# CAN_Bus_Controller_with_LED_Lamp_Drivers.net
KiCad netlist of a schematic drawn in EAGLE
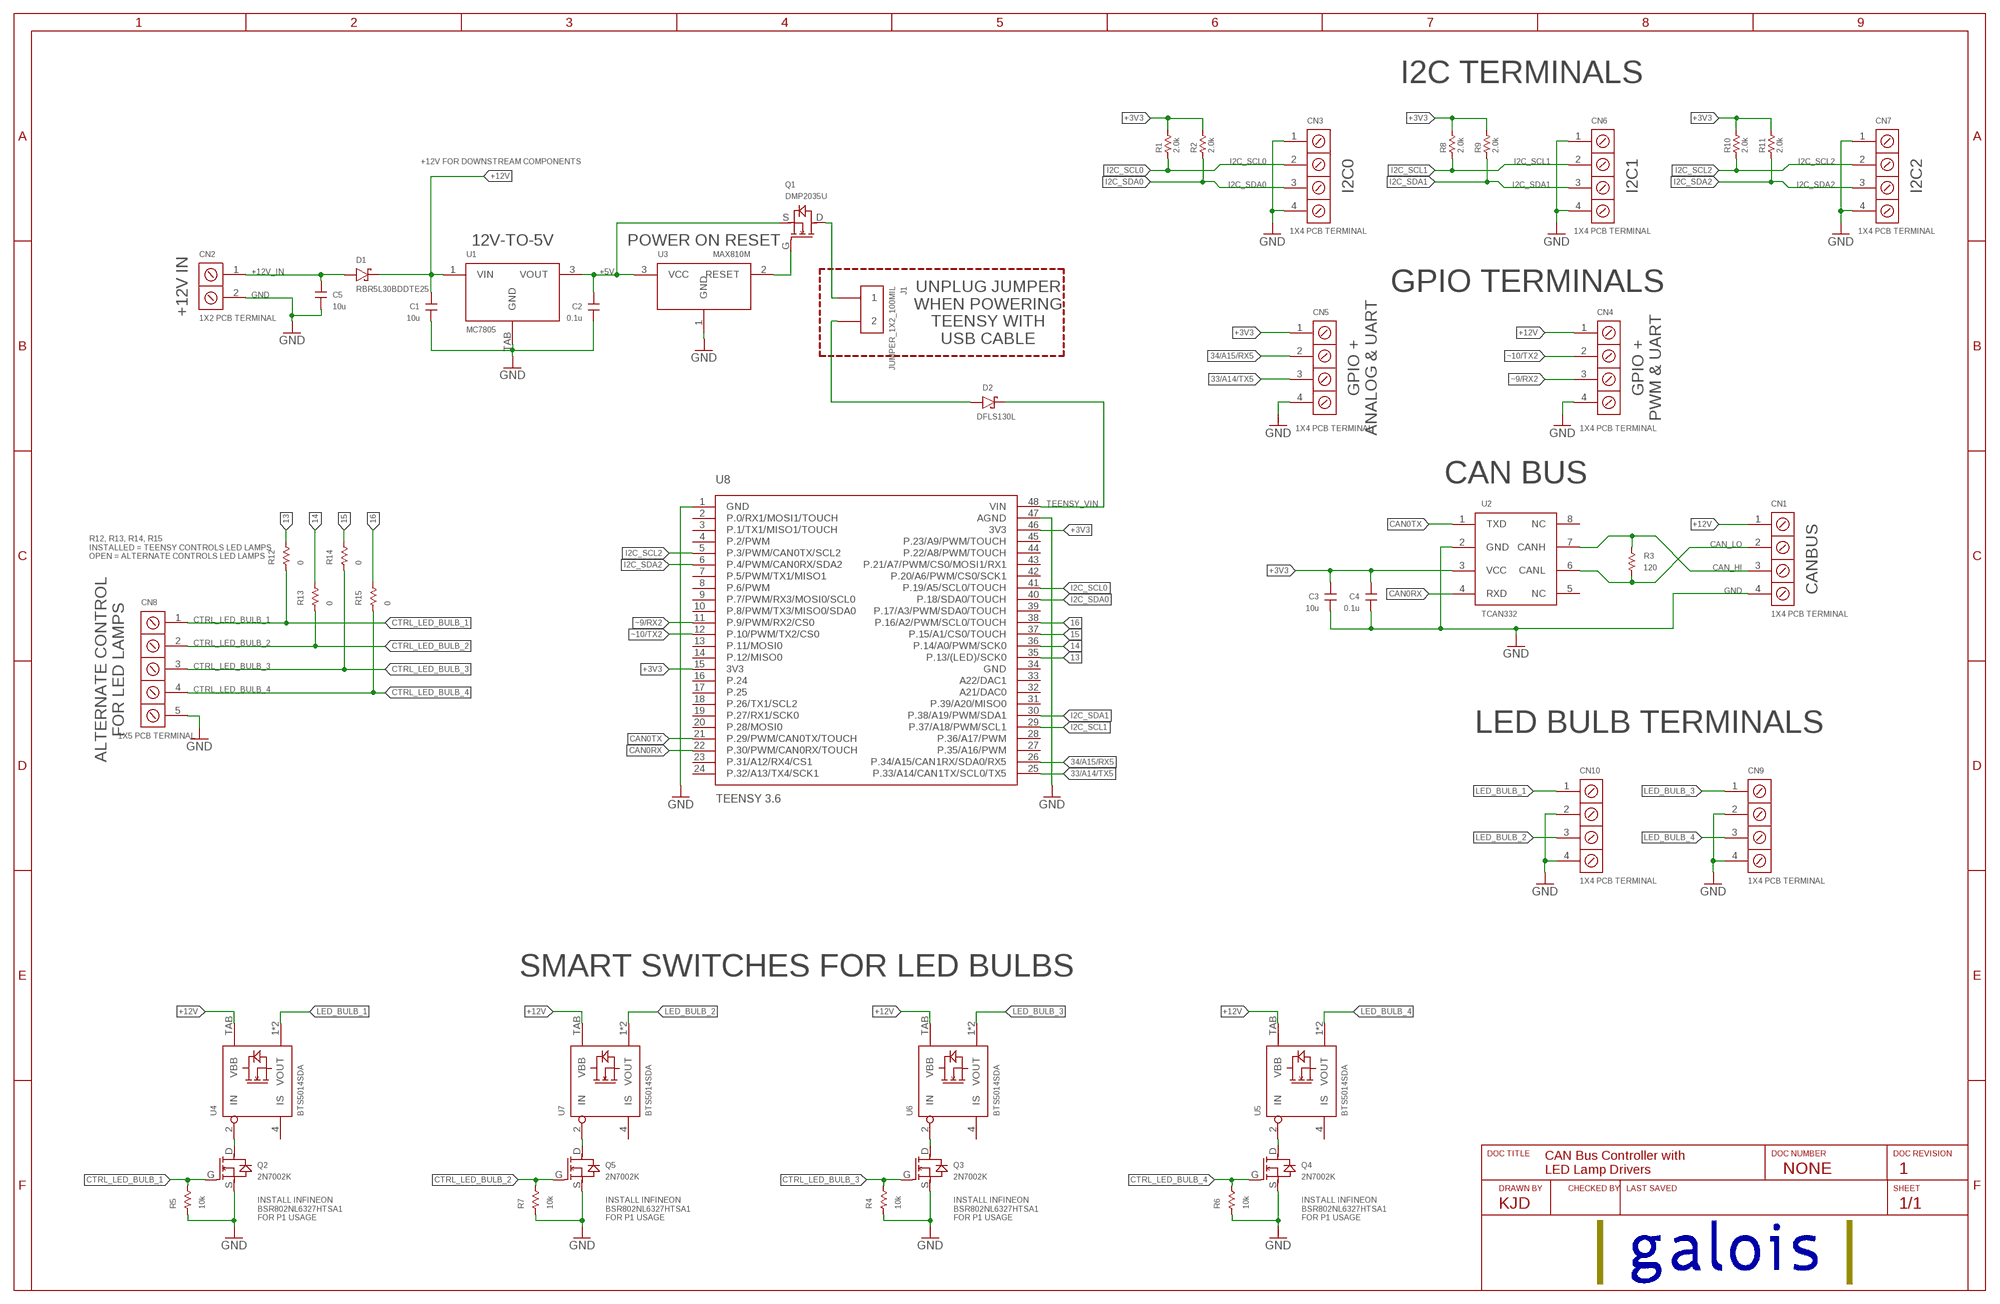
[diagram p0: schematic, sheet 1]

(export (version "E")
  (design (tool "Eeschema 10.0.6"))
  (components
    (comp (ref "C1")
      (value "10u")
      (footprint "eagle-import:EIA1206")
      (fields (field (name "MPN") "CL31A106KBHNNNE"))
      (libsource (lib "eagle-import") (part "C_SMDC1206"))
    )
    (comp (ref "C2")
      (value "0.1u")
      (footprint "eagle-import:EIA0603")
      (fields (field (name "MPN") "CL10B104KA8NNNC"))
      (libsource (lib "eagle-import") (part "C_SMDC0603"))
    )
    (comp (ref "C3")
      (value "10u")
      (footprint "eagle-import:EIA1206")
      (fields (field (name "MPN") "CL31A106KBHNNNE"))
      (libsource (lib "eagle-import") (part "C_SMDC1206"))
    )
    (comp (ref "C4")
      (value "0.1u")
      (footprint "eagle-import:EIA0603")
      (fields (field (name "MPN") "CL10B104KA8NNNC"))
      (libsource (lib "eagle-import") (part "C_SMDC0603"))
    )
    (comp (ref "C5")
      (value "10u")
      (footprint "eagle-import:EIA1206")
      (fields (field (name "MPN") "CL31A106KBHNNNE"))
      (libsource (lib "eagle-import") (part "C_SMDC1206"))
    )
    (comp (ref "CN1")
      (value "1X4 PCB TERMINAL")
      (footprint "eagle-import:PCB_TERM_3.5MM_PITCH_1X4")
      (fields (field (name "MPN") "1984633"))
      (libsource (lib "eagle-import") (part "1984633"))
    )
    (comp (ref "CN2")
      (value "1X2 PCB TERMINAL")
      (footprint "eagle-import:PCB_TERM_3.5MM_PITCH_1X2")
      (fields (field (name "MPN") "1984617"))
      (libsource (lib "eagle-import") (part "1984617"))
    )
    (comp (ref "CN3")
      (value "1X4 PCB TERMINAL")
      (footprint "eagle-import:PCB_TERM_3.5MM_PITCH_1X4")
      (fields (field (name "MPN") "1984633"))
      (libsource (lib "eagle-import") (part "1984633"))
    )
    (comp (ref "CN4")
      (value "1X4 PCB TERMINAL")
      (footprint "eagle-import:PCB_TERM_3.5MM_PITCH_1X4")
      (fields (field (name "MPN") "1984633"))
      (libsource (lib "eagle-import") (part "1984633"))
    )
    (comp (ref "CN5")
      (value "1X4 PCB TERMINAL")
      (footprint "eagle-import:PCB_TERM_3.5MM_PITCH_1X4")
      (fields (field (name "MPN") "1984633"))
      (libsource (lib "eagle-import") (part "1984633"))
    )
    (comp (ref "CN6")
      (value "1X4 PCB TERMINAL")
      (footprint "eagle-import:PCB_TERM_3.5MM_PITCH_1X4")
      (fields (field (name "MPN") "1984633"))
      (libsource (lib "eagle-import") (part "1984633"))
    )
    (comp (ref "CN7")
      (value "1X4 PCB TERMINAL")
      (footprint "eagle-import:PCB_TERM_3.5MM_PITCH_1X4")
      (fields (field (name "MPN") "1984633"))
      (libsource (lib "eagle-import") (part "1984633"))
    )
    (comp (ref "CN8")
      (value "1X5 PCB TERMINAL")
      (footprint "eagle-import:PCB_TERM_3.5MM_PITCH_1X5")
      (fields (field (name "MPN") "1984646"))
      (libsource (lib "eagle-import") (part "1984646"))
    )
    (comp (ref "CN9")
      (value "1X4 PCB TERMINAL")
      (footprint "eagle-import:PCB_TERM_3.5MM_PITCH_1X4")
      (fields (field (name "MPN") "1984633"))
      (libsource (lib "eagle-import") (part "1984633"))
    )
    (comp (ref "CN10")
      (value "1X4 PCB TERMINAL")
      (footprint "eagle-import:PCB_TERM_3.5MM_PITCH_1X4")
      (fields (field (name "MPN") "1984633"))
      (libsource (lib "eagle-import") (part "1984633"))
    )
    (comp (ref "D1")
      (value "RBR5L30BDDTE25")
      (footprint "eagle-import:SMA")
      (fields (field (name "MPN") "RBR5L30BDDTE25"))
      (libsource (lib "eagle-import") (part "SCHOTTKYSMA"))
    )
    (comp (ref "D2")
      (value "DFLS130L")
      (footprint "eagle-import:POWERDI_123")
      (fields (field (name "MPN") "DFLS130L-7"))
      (libsource (lib "eagle-import") (part "SCHOTTKYPOWERDI_123"))
    )
    (comp (ref "J1")
      (value "JUMPER_1X2_100MIL")
      (footprint "eagle-import:1X2_100MIL_THRU")
      (fields (field (name "MPN") "QPC02SXGN-RC"))
      (libsource (lib "eagle-import") (part "1X2"))
    )
    (comp (ref "Q1")
      (value "DMP2035U")
      (footprint "eagle-import:SOT-23-3")
      (fields (field (name "MPN") "DMP2035U-7"))
      (libsource (lib "eagle-import") (part "DMP2035U"))
    )
    (comp (ref "Q2")
      (value "2N7002K")
      (footprint "eagle-import:SOT-23-3")
      (fields (field (name "MPN") "2N7002K-7"))
      (libsource (lib "eagle-import") (part "2N7002K"))
    )
    (comp (ref "Q3")
      (value "2N7002K")
      (footprint "eagle-import:SOT-23-3")
      (fields (field (name "MPN") "2N7002K-7"))
      (libsource (lib "eagle-import") (part "2N7002K"))
    )
    (comp (ref "Q4")
      (value "2N7002K")
      (footprint "eagle-import:SOT-23-3")
      (fields (field (name "MPN") "2N7002K-7"))
      (libsource (lib "eagle-import") (part "2N7002K"))
    )
    (comp (ref "Q5")
      (value "2N7002K")
      (footprint "eagle-import:SOT-23-3")
      (fields (field (name "MPN") "2N7002K-7"))
      (libsource (lib "eagle-import") (part "2N7002K"))
    )
    (comp (ref "R1")
      (value "2.0k")
      (footprint "eagle-import:EIA0603")
      (fields (field (name "MPN") "ERJ-3EKF2001V"))
      (libsource (lib "eagle-import") (part "R_SMDR0603"))
    )
    (comp (ref "R2")
      (value "2.0k")
      (footprint "eagle-import:EIA0603")
      (fields (field (name "MPN") "ERJ-3EKF2001V"))
      (libsource (lib "eagle-import") (part "R_SMDR0603"))
    )
    (comp (ref "R3")
      (value "120")
      (footprint "eagle-import:EIA1210")
      (fields (field (name "MPN") "AC1210FR-07120RL"))
      (libsource (lib "eagle-import") (part "R_SMDR1210"))
    )
    (comp (ref "R4")
      (value "10k")
      (footprint "eagle-import:EIA0603")
      (fields (field (name "MPN") "ERJ-3EKF1002V"))
      (libsource (lib "eagle-import") (part "R_SMDR0603"))
    )
    (comp (ref "R5")
      (value "10k")
      (footprint "eagle-import:EIA0603")
      (fields (field (name "MPN") "ERJ-3EKF1002V"))
      (libsource (lib "eagle-import") (part "R_SMDR0603"))
    )
    (comp (ref "R6")
      (value "10k")
      (footprint "eagle-import:EIA0603")
      (fields (field (name "MPN") "ERJ-3EKF1002V"))
      (libsource (lib "eagle-import") (part "R_SMDR0603"))
    )
    (comp (ref "R7")
      (value "10k")
      (footprint "eagle-import:EIA0603")
      (fields (field (name "MPN") "ERJ-3EKF1002V"))
      (libsource (lib "eagle-import") (part "R_SMDR0603"))
    )
    (comp (ref "R8")
      (value "2.0k")
      (footprint "eagle-import:EIA0603")
      (fields (field (name "MPN") "ERJ-3EKF2001V"))
      (libsource (lib "eagle-import") (part "R_SMDR0603"))
    )
    (comp (ref "R9")
      (value "2.0k")
      (footprint "eagle-import:EIA0603")
      (fields (field (name "MPN") "ERJ-3EKF2001V"))
      (libsource (lib "eagle-import") (part "R_SMDR0603"))
    )
    (comp (ref "R10")
      (value "2.0k")
      (footprint "eagle-import:EIA0603")
      (fields (field (name "MPN") "ERJ-3EKF2001V"))
      (libsource (lib "eagle-import") (part "R_SMDR0603"))
    )
    (comp (ref "R11")
      (value "2.0k")
      (footprint "eagle-import:EIA0603")
      (fields (field (name "MPN") "ERJ-3EKF2001V"))
      (libsource (lib "eagle-import") (part "R_SMDR0603"))
    )
    (comp (ref "R12")
      (value "0")
      (footprint "eagle-import:EIA0603")
      (fields (field (name "MPN") "ERJ-3GEY0R00V"))
      (libsource (lib "eagle-import") (part "R_SMDR0603"))
    )
    (comp (ref "R13")
      (value "0")
      (footprint "eagle-import:EIA0603")
      (fields (field (name "MPN") "ERJ-3GEY0R00V"))
      (libsource (lib "eagle-import") (part "R_SMDR0603"))
    )
    (comp (ref "R14")
      (value "0")
      (footprint "eagle-import:EIA0603")
      (fields (field (name "MPN") "ERJ-3GEY0R00V"))
      (libsource (lib "eagle-import") (part "R_SMDR0603"))
    )
    (comp (ref "R15")
      (value "0")
      (footprint "eagle-import:EIA0603")
      (fields (field (name "MPN") "ERJ-3GEY0R00V"))
      (libsource (lib "eagle-import") (part "R_SMDR0603"))
    )
    (comp (ref "U1")
      (value "MC7805")
      (footprint "eagle-import:DPAK-3")
      (fields (field (name "MPN") "MC7805CDTRKG"))
      (libsource (lib "eagle-import") (part "MC78XX"))
    )
    (comp (ref "U2")
      (value "TCAN332")
      (footprint "eagle-import:SOIC-8")
      (fields (field (name "MPN") "TCAN332DR"))
      (libsource (lib "eagle-import") (part "TCAN332_CANBUS_RXTX"))
    )
    (comp (ref "U3")
      (value "MAX810M")
      (footprint "eagle-import:SOT23-3")
      (fields (field (name "MPN") "MAX810MTRG"))
      (libsource (lib "eagle-import") (part "MAX809/810"))
    )
    (comp (ref "U4")
      (value "BTS5014SDA")
      (footprint "eagle-import:PG-TO252-5-11")
      (fields (field (name "MPN") "BTS5014SDAAUMA1"))
      (libsource (lib "eagle-import") (part "BTS5014SDA"))
    )
    (comp (ref "U5")
      (value "BTS5014SDA")
      (footprint "eagle-import:PG-TO252-5-11")
      (fields (field (name "MPN") "BTS5014SDAAUMA1"))
      (libsource (lib "eagle-import") (part "BTS5014SDA"))
    )
    (comp (ref "U6")
      (value "BTS5014SDA")
      (footprint "eagle-import:PG-TO252-5-11")
      (fields (field (name "MPN") "BTS5014SDAAUMA1"))
      (libsource (lib "eagle-import") (part "BTS5014SDA"))
    )
    (comp (ref "U7")
      (value "BTS5014SDA")
      (footprint "eagle-import:PG-TO252-5-11")
      (fields (field (name "MPN") "BTS5014SDAAUMA1"))
      (libsource (lib "eagle-import") (part "BTS5014SDA"))
    )
    (comp (ref "U8")
      (value "TEENSY 3.6")
      (footprint "eagle-import:TEENSY3.6")
      (libsource (lib "eagle-import") (part "TEENSY3.6NO_UNDER_PINS"))
    )
  )
  (nets
    (net (code "1") (name "+3V3") (class "Default")
      (node (ref "C3") (pin "P$2") (pinfunction "P$2_P$2") (pintype "passive"))
      (node (ref "C4") (pin "P$2") (pinfunction "P$2_P$2") (pintype "passive"))
      (node (ref "CN5") (pin "1") (pinfunction "1_1") (pintype "bidirectional"))
      (node (ref "R1") (pin "P$2") (pinfunction "P$2_P$2") (pintype "passive"))
      (node (ref "R10") (pin "P$2") (pinfunction "P$2_P$2") (pintype "passive"))
      (node (ref "R11") (pin "P$2") (pinfunction "P$2_P$2") (pintype "passive"))
      (node (ref "R2") (pin "P$2") (pinfunction "P$2_P$2") (pintype "passive"))
      (node (ref "R8") (pin "P$2") (pinfunction "P$2_P$2") (pintype "passive"))
      (node (ref "R9") (pin "P$2") (pinfunction "P$2_P$2") (pintype "passive"))
      (node (ref "U2") (pin "3") (pinfunction "VCC_3") (pintype "bidirectional"))
      (node (ref "U8") (pin "15") (pinfunction "3V3_15") (pintype "bidirectional"))
      (node (ref "U8") (pin "46") (pinfunction "3V3_46") (pintype "bidirectional"))
    )
    (net (code "2") (name "+12V") (class "Default")
      (node (ref "C1") (pin "P$2") (pinfunction "P$2_P$2") (pintype "passive"))
      (node (ref "CN1") (pin "1") (pinfunction "1_1") (pintype "bidirectional"))
      (node (ref "CN4") (pin "1") (pinfunction "1_1") (pintype "bidirectional"))
      (node (ref "D1") (pin "C") (pinfunction "C_C") (pintype "bidirectional"))
      (node (ref "U1") (pin "1") (pinfunction "VIN_1") (pintype "bidirectional"))
      (node (ref "U4") (pin "TAB") (pinfunction "VBB_TAB") (pintype "bidirectional"))
      (node (ref "U5") (pin "TAB") (pinfunction "VBB_TAB") (pintype "bidirectional"))
      (node (ref "U6") (pin "TAB") (pinfunction "VBB_TAB") (pintype "bidirectional"))
      (node (ref "U7") (pin "TAB") (pinfunction "VBB_TAB") (pintype "bidirectional"))
    )
    (net (code "3") (name "/+5V") (class "Default")
      (node (ref "C2") (pin "P$2") (pinfunction "P$2_P$2") (pintype "passive"))
      (node (ref "Q1") (pin "S") (pinfunction "S_S") (pintype "bidirectional"))
      (node (ref "U1") (pin "3") (pinfunction "VOUT_3") (pintype "bidirectional"))
      (node (ref "U3") (pin "3") (pinfunction "VCC_3") (pintype "bidirectional"))
    )
    (net (code "4") (name "/+12V_IN") (class "Default")
      (node (ref "C5") (pin "P$2") (pinfunction "P$2_P$2") (pintype "passive"))
      (node (ref "CN2") (pin "1") (pinfunction "1_1") (pintype "bidirectional"))
      (node (ref "D1") (pin "A") (pinfunction "A_A") (pintype "bidirectional"))
    )
    (net (code "5") (name "/CAN_HI") (class "Default")
      (node (ref "CN1") (pin "3") (pinfunction "3_3") (pintype "bidirectional"))
      (node (ref "R3") (pin "P$2") (pinfunction "P$2_P$2") (pintype "passive"))
      (node (ref "U2") (pin "7") (pinfunction "CANH_7") (pintype "bidirectional"))
    )
    (net (code "6") (name "/CAN_LO") (class "Default")
      (node (ref "CN1") (pin "2") (pinfunction "2_2") (pintype "bidirectional"))
      (node (ref "R3") (pin "P$1") (pinfunction "P$1_P$1") (pintype "passive"))
      (node (ref "U2") (pin "6") (pinfunction "CANL_6") (pintype "bidirectional"))
    )
    (net (code "7") (name "/TEENSY_VIN") (class "Default")
      (node (ref "D2") (pin "C") (pinfunction "C_C") (pintype "bidirectional"))
      (node (ref "U8") (pin "48") (pinfunction "VIN_48") (pintype "bidirectional"))
    )
    (net (code "8") (name "/~{9{slash}RX2}") (class "Default")
      (node (ref "CN4") (pin "3") (pinfunction "3_3") (pintype "bidirectional"))
      (node (ref "U8") (pin "11") (pinfunction "P.9/PWM/RX2/CS0_11") (pintype "bidirectional"))
    )
    (net (code "9") (name "/~{10{slash}TX2}") (class "Default")
      (node (ref "CN4") (pin "2") (pinfunction "2_2") (pintype "bidirectional"))
      (node (ref "U8") (pin "12") (pinfunction "P.10/PWM/TX2/CS0_12") (pintype "bidirectional"))
    )
    (net (code "10") (name "13") (class "Default")
      (node (ref "R12") (pin "P$2") (pinfunction "P$2_P$2") (pintype "passive"))
      (node (ref "U8") (pin "35") (pinfunction "P.13/(LED)/SCK0_35") (pintype "bidirectional"))
    )
    (net (code "11") (name "14") (class "Default")
      (node (ref "R13") (pin "P$2") (pinfunction "P$2_P$2") (pintype "passive"))
      (node (ref "U8") (pin "36") (pinfunction "P.14/A0/PWM/SCK0_36") (pintype "bidirectional"))
    )
    (net (code "12") (name "15") (class "Default")
      (node (ref "R14") (pin "P$2") (pinfunction "P$2_P$2") (pintype "passive"))
      (node (ref "U8") (pin "37") (pinfunction "P.15/A1/CS0/TOUCH_37") (pintype "bidirectional"))
    )
    (net (code "13") (name "16") (class "Default")
      (node (ref "R15") (pin "P$2") (pinfunction "P$2_P$2") (pintype "passive"))
      (node (ref "U8") (pin "38") (pinfunction "P.16/A2/PWM/SCL0/TOUCH_38") (pintype "bidirectional"))
    )
    (net (code "14") (name "33{slash}A14{slash}TX5") (class "Default")
      (node (ref "CN5") (pin "3") (pinfunction "3_3") (pintype "bidirectional"))
      (node (ref "U8") (pin "25") (pinfunction "P.33/A14/CAN1TX/SCL0/TX5_25") (pintype "bidirectional"))
    )
    (net (code "15") (name "34{slash}A15{slash}RX5") (class "Default")
      (node (ref "CN5") (pin "2") (pinfunction "2_2") (pintype "bidirectional"))
      (node (ref "U8") (pin "26") (pinfunction "P.34/A15/CAN1RX/SDA0/RX5_26") (pintype "bidirectional"))
    )
    (net (code "16") (name "CAN0RX") (class "Default")
      (node (ref "U2") (pin "4") (pinfunction "RXD_4") (pintype "bidirectional"))
      (node (ref "U8") (pin "22") (pinfunction "P.30/PWM/CAN0RX/TOUCH_22") (pintype "bidirectional"))
    )
    (net (code "17") (name "CAN0TX") (class "Default")
      (node (ref "U2") (pin "1") (pinfunction "TXD_1") (pintype "bidirectional"))
      (node (ref "U8") (pin "21") (pinfunction "P.29/PWM/CAN0TX/TOUCH_21") (pintype "bidirectional"))
    )
    (net (code "18") (name "CTRL_LED_BULB_1") (class "Default")
      (node (ref "CN8") (pin "1") (pinfunction "1_1") (pintype "bidirectional"))
      (node (ref "Q2") (pin "G") (pinfunction "G_G") (pintype "bidirectional"))
      (node (ref "R12") (pin "P$1") (pinfunction "P$1_P$1") (pintype "passive"))
      (node (ref "R5") (pin "P$2") (pinfunction "P$2_P$2") (pintype "passive"))
    )
    (net (code "19") (name "CTRL_LED_BULB_2") (class "Default")
      (node (ref "CN8") (pin "2") (pinfunction "2_2") (pintype "bidirectional"))
      (node (ref "Q5") (pin "G") (pinfunction "G_G") (pintype "bidirectional"))
      (node (ref "R13") (pin "P$1") (pinfunction "P$1_P$1") (pintype "passive"))
      (node (ref "R7") (pin "P$2") (pinfunction "P$2_P$2") (pintype "passive"))
    )
    (net (code "20") (name "CTRL_LED_BULB_3") (class "Default")
      (node (ref "CN8") (pin "3") (pinfunction "3_3") (pintype "bidirectional"))
      (node (ref "Q3") (pin "G") (pinfunction "G_G") (pintype "bidirectional"))
      (node (ref "R14") (pin "P$1") (pinfunction "P$1_P$1") (pintype "passive"))
      (node (ref "R4") (pin "P$2") (pinfunction "P$2_P$2") (pintype "passive"))
    )
    (net (code "21") (name "CTRL_LED_BULB_4") (class "Default")
      (node (ref "CN8") (pin "4") (pinfunction "4_4") (pintype "bidirectional"))
      (node (ref "Q4") (pin "G") (pinfunction "G_G") (pintype "bidirectional"))
      (node (ref "R15") (pin "P$1") (pinfunction "P$1_P$1") (pintype "passive"))
      (node (ref "R6") (pin "P$2") (pinfunction "P$2_P$2") (pintype "passive"))
    )
    (net (code "22") (name "GND") (class "Default")
      (node (ref "C1") (pin "P$1") (pinfunction "P$1_P$1") (pintype "passive"))
      (node (ref "C2") (pin "P$1") (pinfunction "P$1_P$1") (pintype "passive"))
      (node (ref "C3") (pin "P$1") (pinfunction "P$1_P$1") (pintype "passive"))
      (node (ref "C4") (pin "P$1") (pinfunction "P$1_P$1") (pintype "passive"))
      (node (ref "C5") (pin "P$1") (pinfunction "P$1_P$1") (pintype "passive"))
      (node (ref "CN1") (pin "4") (pinfunction "4_4") (pintype "bidirectional"))
      (node (ref "CN10") (pin "2") (pinfunction "2_2") (pintype "bidirectional"))
      (node (ref "CN10") (pin "4") (pinfunction "4_4") (pintype "bidirectional"))
      (node (ref "CN2") (pin "2") (pinfunction "2_2") (pintype "bidirectional"))
      (node (ref "CN3") (pin "1") (pinfunction "1_1") (pintype "bidirectional"))
      (node (ref "CN3") (pin "4") (pinfunction "4_4") (pintype "bidirectional"))
      (node (ref "CN4") (pin "4") (pinfunction "4_4") (pintype "bidirectional"))
      (node (ref "CN5") (pin "4") (pinfunction "4_4") (pintype "bidirectional"))
      (node (ref "CN6") (pin "1") (pinfunction "1_1") (pintype "bidirectional"))
      (node (ref "CN6") (pin "4") (pinfunction "4_4") (pintype "bidirectional"))
      (node (ref "CN7") (pin "1") (pinfunction "1_1") (pintype "bidirectional"))
      (node (ref "CN7") (pin "4") (pinfunction "4_4") (pintype "bidirectional"))
      (node (ref "CN8") (pin "5") (pinfunction "5_5") (pintype "bidirectional"))
      (node (ref "CN9") (pin "2") (pinfunction "2_2") (pintype "bidirectional"))
      (node (ref "CN9") (pin "4") (pinfunction "4_4") (pintype "bidirectional"))
      (node (ref "Q2") (pin "S") (pinfunction "S_S") (pintype "bidirectional"))
      (node (ref "Q3") (pin "S") (pinfunction "S_S") (pintype "bidirectional"))
      (node (ref "Q4") (pin "S") (pinfunction "S_S") (pintype "bidirectional"))
      (node (ref "Q5") (pin "S") (pinfunction "S_S") (pintype "bidirectional"))
      (node (ref "R4") (pin "P$1") (pinfunction "P$1_P$1") (pintype "passive"))
      (node (ref "R5") (pin "P$1") (pinfunction "P$1_P$1") (pintype "passive"))
      (node (ref "R6") (pin "P$1") (pinfunction "P$1_P$1") (pintype "passive"))
      (node (ref "R7") (pin "P$1") (pinfunction "P$1_P$1") (pintype "passive"))
      (node (ref "U1") (pin "TAB") (pinfunction "GND_TAB") (pintype "bidirectional"))
      (node (ref "U2") (pin "2") (pinfunction "GND_2") (pintype "bidirectional"))
      (node (ref "U3") (pin "1") (pinfunction "GND_1") (pintype "bidirectional"))
      (node (ref "U8") (pin "1") (pinfunction "GND_1") (pintype "bidirectional"))
      (node (ref "U8") (pin "47") (pinfunction "AGND_47") (pintype "bidirectional"))
    )
    (net (code "23") (name "I2C_SCL0") (class "Default")
      (node (ref "CN3") (pin "2") (pinfunction "2_2") (pintype "bidirectional"))
      (node (ref "R1") (pin "P$1") (pinfunction "P$1_P$1") (pintype "passive"))
      (node (ref "U8") (pin "41") (pinfunction "P.19/A5/SCL0/TOUCH_41") (pintype "bidirectional"))
    )
    (net (code "24") (name "I2C_SCL1") (class "Default")
      (node (ref "CN6") (pin "2") (pinfunction "2_2") (pintype "bidirectional"))
      (node (ref "R8") (pin "P$1") (pinfunction "P$1_P$1") (pintype "passive"))
      (node (ref "U8") (pin "29") (pinfunction "P.37/A18/PWM/SCL1_29") (pintype "bidirectional"))
    )
    (net (code "25") (name "I2C_SCL2") (class "Default")
      (node (ref "CN7") (pin "2") (pinfunction "2_2") (pintype "bidirectional"))
      (node (ref "R10") (pin "P$1") (pinfunction "P$1_P$1") (pintype "passive"))
      (node (ref "U8") (pin "5") (pinfunction "P.3/PWM/CAN0TX/SCL2_5") (pintype "bidirectional"))
    )
    (net (code "26") (name "I2C_SDA0") (class "Default")
      (node (ref "CN3") (pin "3") (pinfunction "3_3") (pintype "bidirectional"))
      (node (ref "R2") (pin "P$1") (pinfunction "P$1_P$1") (pintype "passive"))
      (node (ref "U8") (pin "40") (pinfunction "P.18/SDA0/TOUCH_40") (pintype "bidirectional"))
    )
    (net (code "27") (name "I2C_SDA1") (class "Default")
      (node (ref "CN6") (pin "3") (pinfunction "3_3") (pintype "bidirectional"))
      (node (ref "R9") (pin "P$1") (pinfunction "P$1_P$1") (pintype "passive"))
      (node (ref "U8") (pin "30") (pinfunction "P.38/A19/PWM/SDA1_30") (pintype "bidirectional"))
    )
    (net (code "28") (name "I2C_SDA2") (class "Default")
      (node (ref "CN7") (pin "3") (pinfunction "3_3") (pintype "bidirectional"))
      (node (ref "R11") (pin "P$1") (pinfunction "P$1_P$1") (pintype "passive"))
      (node (ref "U8") (pin "6") (pinfunction "P.4/PWM/CAN0RX/SDA2_6") (pintype "bidirectional"))
    )
    (net (code "29") (name "LED_BULB_1") (class "Default")
      (node (ref "CN10") (pin "1") (pinfunction "1_1") (pintype "bidirectional"))
      (node (ref "U4") (pin "1") (pinfunction "VOUT_1") (pintype "bidirectional"))
      (node (ref "U4") (pin "5") (pinfunction "VOUT_5") (pintype "bidirectional"))
    )
    (net (code "30") (name "LED_BULB_2") (class "Default")
      (node (ref "CN10") (pin "3") (pinfunction "3_3") (pintype "bidirectional"))
      (node (ref "U7") (pin "1") (pinfunction "VOUT_1") (pintype "bidirectional"))
      (node (ref "U7") (pin "5") (pinfunction "VOUT_5") (pintype "bidirectional"))
    )
    (net (code "31") (name "LED_BULB_3") (class "Default")
      (node (ref "CN9") (pin "1") (pinfunction "1_1") (pintype "bidirectional"))
      (node (ref "U6") (pin "1") (pinfunction "VOUT_1") (pintype "bidirectional"))
      (node (ref "U6") (pin "5") (pinfunction "VOUT_5") (pintype "bidirectional"))
    )
    (net (code "32") (name "LED_BULB_4") (class "Default")
      (node (ref "CN9") (pin "3") (pinfunction "3_3") (pintype "bidirectional"))
      (node (ref "U5") (pin "1") (pinfunction "VOUT_1") (pintype "bidirectional"))
      (node (ref "U5") (pin "5") (pinfunction "VOUT_5") (pintype "bidirectional"))
    )
    (net (code "33") (name "Net-(D2-PadA)") (class "Default")
      (node (ref "D2") (pin "A") (pinfunction "A_A") (pintype "bidirectional"))
      (node (ref "J1") (pin "2") (pinfunction "2_2") (pintype "bidirectional"))
    )
    (net (code "34") (name "Net-(J1-Pad1)") (class "Default")
      (node (ref "J1") (pin "1") (pinfunction "1_1") (pintype "bidirectional"))
      (node (ref "Q1") (pin "D") (pinfunction "D_D") (pintype "bidirectional"))
    )
    (net (code "35") (name "Net-(U3-RESET)") (class "Default")
      (node (ref "Q1") (pin "G") (pinfunction "G_G") (pintype "bidirectional"))
      (node (ref "U3") (pin "2") (pinfunction "RESET_2") (pintype "bidirectional"))
    )
    (net (code "36") (name "Net-(U4-IN)") (class "Default")
      (node (ref "Q2") (pin "D") (pinfunction "D_D") (pintype "bidirectional"))
      (node (ref "U4") (pin "2") (pinfunction "IN_2") (pintype "bidirectional"))
    )
    (net (code "37") (name "Net-(U5-IN)") (class "Default")
      (node (ref "Q4") (pin "D") (pinfunction "D_D") (pintype "bidirectional"))
      (node (ref "U5") (pin "2") (pinfunction "IN_2") (pintype "bidirectional"))
    )
    (net (code "38") (name "Net-(U6-IN)") (class "Default")
      (node (ref "Q3") (pin "D") (pinfunction "D_D") (pintype "bidirectional"))
      (node (ref "U6") (pin "2") (pinfunction "IN_2") (pintype "bidirectional"))
    )
    (net (code "39") (name "Net-(U7-IN)") (class "Default")
      (node (ref "Q5") (pin "D") (pinfunction "D_D") (pintype "bidirectional"))
      (node (ref "U7") (pin "2") (pinfunction "IN_2") (pintype "bidirectional"))
    )
    (net (code "40") (name "unconnected-(U2-NC-Pad5)") (class "Default")
      (node (ref "U2") (pin "5") (pinfunction "NC_5") (pintype "bidirectional"))
    )
    (net (code "41") (name "unconnected-(U2-NC-Pad8)") (class "Default")
      (node (ref "U2") (pin "8") (pinfunction "NC_8") (pintype "bidirectional"))
    )
    (net (code "42") (name "unconnected-(U4-IS-Pad4)") (class "Default")
      (node (ref "U4") (pin "4") (pinfunction "IS_4") (pintype "bidirectional"))
    )
    (net (code "43") (name "unconnected-(U5-IS-Pad4)") (class "Default")
      (node (ref "U5") (pin "4") (pinfunction "IS_4") (pintype "bidirectional"))
    )
    (net (code "44") (name "unconnected-(U6-IS-Pad4)") (class "Default")
      (node (ref "U6") (pin "4") (pinfunction "IS_4") (pintype "bidirectional"))
    )
    (net (code "45") (name "unconnected-(U7-IS-Pad4)") (class "Default")
      (node (ref "U7") (pin "4") (pinfunction "IS_4") (pintype "bidirectional"))
    )
    (net (code "46") (name "unconnected-(U8-A21{slash}DAC0-Pad32)") (class "Default")
      (node (ref "U8") (pin "32") (pinfunction "A21/DAC0_32") (pintype "bidirectional"))
    )
    (net (code "47") (name "unconnected-(U8-A22{slash}DAC1-Pad33)") (class "Default")
      (node (ref "U8") (pin "33") (pinfunction "A22/DAC1_33") (pintype "bidirectional"))
    )
    (net (code "48") (name "unconnected-(U8-GND-Pad34)") (class "Default")
      (node (ref "U8") (pin "34") (pinfunction "GND_34") (pintype "bidirectional"))
    )
    (net (code "49") (name "unconnected-(U8-P.0{slash}RX1{slash}MOSI1{slash}TOUCH-Pad2)") (class "Default")
      (node (ref "U8") (pin "2") (pinfunction "P.0/RX1/MOSI1/TOUCH_2") (pintype "bidirectional"))
    )
    (net (code "50") (name "unconnected-(U8-P.1{slash}TX1{slash}MISO1{slash}TOUCH-Pad3)") (class "Default")
      (node (ref "U8") (pin "3") (pinfunction "P.1/TX1/MISO1/TOUCH_3") (pintype "bidirectional"))
    )
    (net (code "51") (name "unconnected-(U8-P.2{slash}PWM-Pad4)") (class "Default")
      (node (ref "U8") (pin "4") (pinfunction "P.2/PWM_4") (pintype "bidirectional"))
    )
    (net (code "52") (name "unconnected-(U8-P.5{slash}PWM{slash}TX1{slash}MISO1-Pad7)") (class "Default")
      (node (ref "U8") (pin "7") (pinfunction "P.5/PWM/TX1/MISO1_7") (pintype "bidirectional"))
    )
    (net (code "53") (name "unconnected-(U8-P.6{slash}PWM-Pad8)") (class "Default")
      (node (ref "U8") (pin "8") (pinfunction "P.6/PWM_8") (pintype "bidirectional"))
    )
    (net (code "54") (name "unconnected-(U8-P.7{slash}PWM{slash}RX3{slash}MOSI0{slash}SCL0-Pad9)") (class "Default")
      (node (ref "U8") (pin "9") (pinfunction "P.7/PWM/RX3/MOSI0/SCL0_9") (pintype "bidirectional"))
    )
    (net (code "55") (name "unconnected-(U8-P.8{slash}PWM{slash}TX3{slash}MISO0{slash}SDA0-Pad10)") (class "Default")
      (node (ref "U8") (pin "10") (pinfunction "P.8/PWM/TX3/MISO0/SDA0_10") (pintype "bidirectional"))
    )
    (net (code "56") (name "unconnected-(U8-P.11{slash}MOSI0-Pad13)") (class "Default")
      (node (ref "U8") (pin "13") (pinfunction "P.11/MOSI0_13") (pintype "bidirectional"))
    )
    (net (code "57") (name "unconnected-(U8-P.12{slash}MISO0-Pad14)") (class "Default")
      (node (ref "U8") (pin "14") (pinfunction "P.12/MISO0_14") (pintype "bidirectional"))
    )
    (net (code "58") (name "unconnected-(U8-P.17{slash}A3{slash}PWM{slash}SDA0{slash}TOUCH-Pad39)") (class "Default")
      (node (ref "U8") (pin "39") (pinfunction "P.17/A3/PWM/SDA0/TOUCH_39") (pintype "bidirectional"))
    )
    (net (code "59") (name "unconnected-(U8-P.20{slash}A6{slash}PWM{slash}CS0{slash}SCK1-Pad42)") (class "Default")
      (node (ref "U8") (pin "42") (pinfunction "P.20/A6/PWM/CS0/SCK1_42") (pintype "bidirectional"))
    )
    (net (code "60") (name "unconnected-(U8-P.21{slash}A7{slash}PWM{slash}CS0{slash}MOSI1{slash}RX1-Pad43)") (class "Default")
      (node (ref "U8") (pin "43") (pinfunction "P.21/A7/PWM/CS0/MOSI1/RX1_43") (pintype "bidirectional"))
    )
    (net (code "61") (name "unconnected-(U8-P.22{slash}A8{slash}PWM{slash}TOUCH-Pad44)") (class "Default")
      (node (ref "U8") (pin "44") (pinfunction "P.22/A8/PWM/TOUCH_44") (pintype "bidirectional"))
    )
    (net (code "62") (name "unconnected-(U8-P.23{slash}A9{slash}PWM{slash}TOUCH-Pad45)") (class "Default")
      (node (ref "U8") (pin "45") (pinfunction "P.23/A9/PWM/TOUCH_45") (pintype "bidirectional"))
    )
    (net (code "63") (name "unconnected-(U8-P.24-Pad16)") (class "Default")
      (node (ref "U8") (pin "16") (pinfunction "P.24_16") (pintype "bidirectional"))
    )
    (net (code "64") (name "unconnected-(U8-P.25-Pad17)") (class "Default")
      (node (ref "U8") (pin "17") (pinfunction "P.25_17") (pintype "bidirectional"))
    )
    (net (code "65") (name "unconnected-(U8-P.26{slash}TX1{slash}SCL2-Pad18)") (class "Default")
      (node (ref "U8") (pin "18") (pinfunction "P.26/TX1/SCL2_18") (pintype "bidirectional"))
    )
    (net (code "66") (name "unconnected-(U8-P.27{slash}RX1{slash}SCK0-Pad19)") (class "Default")
      (node (ref "U8") (pin "19") (pinfunction "P.27/RX1/SCK0_19") (pintype "bidirectional"))
    )
    (net (code "67") (name "unconnected-(U8-P.28{slash}MOSI0-Pad20)") (class "Default")
      (node (ref "U8") (pin "20") (pinfunction "P.28/MOSI0_20") (pintype "bidirectional"))
    )
    (net (code "68") (name "unconnected-(U8-P.31{slash}A12{slash}RX4{slash}CS1-Pad23)") (class "Default")
      (node (ref "U8") (pin "23") (pinfunction "P.31/A12/RX4/CS1_23") (pintype "bidirectional"))
    )
    (net (code "69") (name "unconnected-(U8-P.32{slash}A13{slash}TX4{slash}SCK1-Pad24)") (class "Default")
      (node (ref "U8") (pin "24") (pinfunction "P.32/A13/TX4/SCK1_24") (pintype "bidirectional"))
    )
    (net (code "70") (name "unconnected-(U8-P.35{slash}A16{slash}PWM-Pad27)") (class "Default")
      (node (ref "U8") (pin "27") (pinfunction "P.35/A16/PWM_27") (pintype "bidirectional"))
    )
    (net (code "71") (name "unconnected-(U8-P.36{slash}A17{slash}PWM-Pad28)") (class "Default")
      (node (ref "U8") (pin "28") (pinfunction "P.36/A17/PWM_28") (pintype "bidirectional"))
    )
    (net (code "72") (name "unconnected-(U8-P.39{slash}A20{slash}MISO0-Pad31)") (class "Default")
      (node (ref "U8") (pin "31") (pinfunction "P.39/A20/MISO0_31") (pintype "bidirectional"))
    )
  )
)
